# POWER_Ctrl.net
KiCad netlist of a schematic drawn in Altium Designer
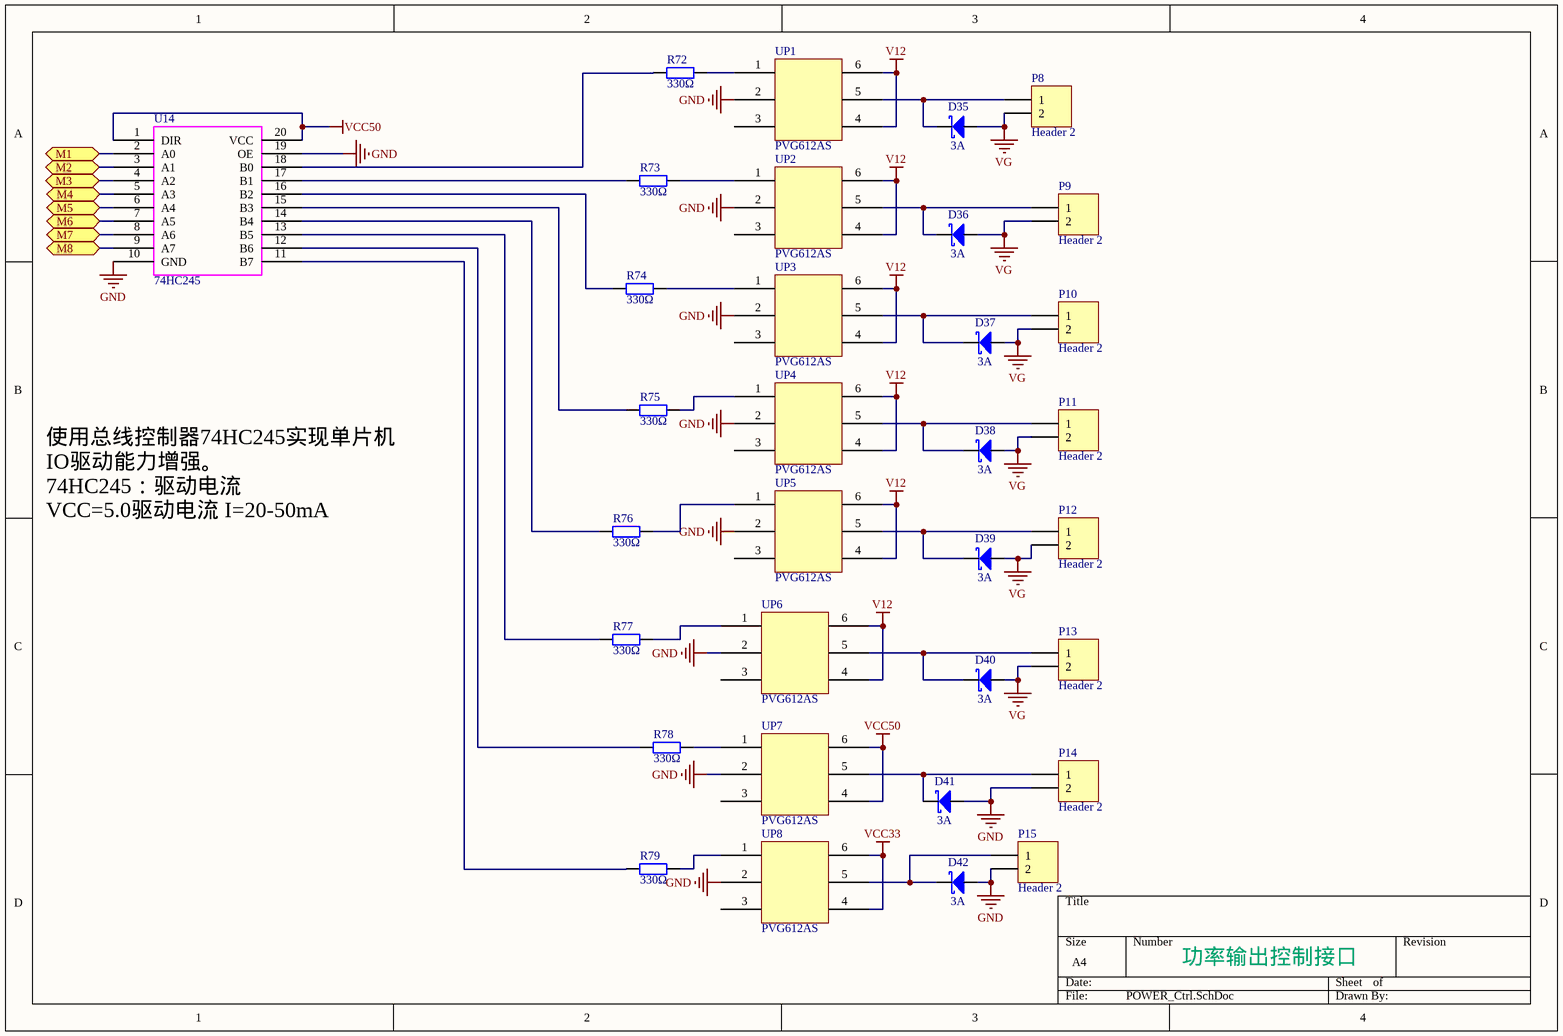
[diagram p0: POWER_Ctrl.SchDoc]

(export (version "E")
  (design (tool "Eeschema 10.0.6"))
  (components
    (comp (ref "D35")
      (value "DiodeSchottky")
      (footprint "SMA")
      (description "Godzilla")
      (fields
        (field (name "GENERACPARTNUMBER") "Temp0036")
        (field (name "MANUFACTURER") "MCC")
        (field (name "DIO CURRENT") "3A")
      )
      (libsource (lib "Jiaoyanyi") (part "DiodeSchottky"))
    )
    (comp (ref "D36")
      (value "DiodeSchottky")
      (footprint "SMA")
      (description "Godzilla")
      (fields
        (field (name "GENERACPARTNUMBER") "Temp0036")
        (field (name "MANUFACTURER") "MCC")
        (field (name "DIO CURRENT") "3A")
      )
      (libsource (lib "Jiaoyanyi") (part "DiodeSchottky"))
    )
    (comp (ref "D37")
      (value "DiodeSchottky")
      (footprint "SMA")
      (description "Godzilla")
      (fields
        (field (name "GENERACPARTNUMBER") "Temp0036")
        (field (name "MANUFACTURER") "MCC")
        (field (name "DIO CURRENT") "3A")
      )
      (libsource (lib "Jiaoyanyi") (part "DiodeSchottky"))
    )
    (comp (ref "D38")
      (value "DiodeSchottky")
      (footprint "SMA")
      (description "Godzilla")
      (fields
        (field (name "GENERACPARTNUMBER") "Temp0036")
        (field (name "MANUFACTURER") "MCC")
        (field (name "DIO CURRENT") "3A")
      )
      (libsource (lib "Jiaoyanyi") (part "DiodeSchottky"))
    )
    (comp (ref "D39")
      (value "DiodeSchottky")
      (footprint "SMA")
      (description "Godzilla")
      (fields
        (field (name "GENERACPARTNUMBER") "Temp0036")
        (field (name "MANUFACTURER") "MCC")
        (field (name "DIO CURRENT") "3A")
      )
      (libsource (lib "Jiaoyanyi") (part "DiodeSchottky"))
    )
    (comp (ref "D40")
      (value "DiodeSchottky")
      (footprint "SMA")
      (description "Godzilla")
      (fields
        (field (name "GENERACPARTNUMBER") "Temp0036")
        (field (name "MANUFACTURER") "MCC")
        (field (name "DIO CURRENT") "3A")
      )
      (libsource (lib "Jiaoyanyi") (part "DiodeSchottky"))
    )
    (comp (ref "D41")
      (value "DiodeSchottky")
      (footprint "SMA")
      (description "Godzilla")
      (fields
        (field (name "GENERACPARTNUMBER") "Temp0036")
        (field (name "MANUFACTURER") "MCC")
        (field (name "DIO CURRENT") "3A")
      )
      (libsource (lib "Jiaoyanyi") (part "DiodeSchottky"))
    )
    (comp (ref "D42")
      (value "DiodeSchottky")
      (footprint "SMA")
      (description "Godzilla")
      (fields
        (field (name "GENERACPARTNUMBER") "Temp0036")
        (field (name "MANUFACTURER") "MCC")
        (field (name "DIO CURRENT") "3A")
      )
      (libsource (lib "Jiaoyanyi") (part "DiodeSchottky"))
    )
    (comp (ref "P8")
      (value "Header 2")
      (footprint "3.81-2P")
      (description "Header, 2-Pin")
      (fields (field (name "PUBLISHER") "Altium Limited"))
      (libsource (lib "Miscellaneous Connectors") (part "Header 2"))
    )
    (comp (ref "P9")
      (value "Header 2")
      (footprint "3.81-2P")
      (description "Header, 2-Pin")
      (fields (field (name "PUBLISHER") "Altium Limited"))
      (libsource (lib "Miscellaneous Connectors") (part "Header 2"))
    )
    (comp (ref "P10")
      (value "Header 2")
      (footprint "3.81-2P")
      (description "Header, 2-Pin")
      (fields (field (name "PUBLISHER") "Altium Limited"))
      (libsource (lib "Miscellaneous Connectors") (part "Header 2"))
    )
    (comp (ref "P11")
      (value "Header 2")
      (footprint "3.81-2P")
      (description "Header, 2-Pin")
      (fields (field (name "PUBLISHER") "Altium Limited"))
      (libsource (lib "Miscellaneous Connectors") (part "Header 2"))
    )
    (comp (ref "P12")
      (value "Header 2")
      (footprint "3.81-2P")
      (description "Header, 2-Pin")
      (fields (field (name "PUBLISHER") "Altium Limited"))
      (libsource (lib "Miscellaneous Connectors") (part "Header 2"))
    )
    (comp (ref "P13")
      (value "Header 2")
      (footprint "3.81-2P")
      (description "Header, 2-Pin")
      (fields (field (name "PUBLISHER") "Altium Limited"))
      (libsource (lib "Miscellaneous Connectors") (part "Header 2"))
    )
    (comp (ref "P14")
      (value "Header 2")
      (footprint "3.81-2P")
      (description "Header, 2-Pin")
      (fields (field (name "PUBLISHER") "Altium Limited"))
      (libsource (lib "Miscellaneous Connectors") (part "Header 2"))
    )
    (comp (ref "P15")
      (value "Header 2")
      (footprint "3.81-2P")
      (description "Header, 2-Pin")
      (fields (field (name "PUBLISHER") "Altium Limited"))
      (libsource (lib "Miscellaneous Connectors") (part "Header 2"))
    )
    (comp (ref "R72")
      (value "330Ω")
      (footprint "1206")
      (description "Resistor")
      (fields (field (name "Comment") "Res2") (field (name "PUBLISHER") "Altium Limited"))
      (libsource (lib "Miscellaneous Devices") (part "Res2"))
    )
    (comp (ref "R73")
      (value "330Ω")
      (footprint "1206")
      (description "Resistor")
      (fields (field (name "Comment") "Res2") (field (name "PUBLISHER") "Altium Limited"))
      (libsource (lib "Miscellaneous Devices") (part "Res2"))
    )
    (comp (ref "R74")
      (value "330Ω")
      (footprint "1206")
      (description "Resistor")
      (fields (field (name "Comment") "Res2") (field (name "PUBLISHER") "Altium Limited"))
      (libsource (lib "Miscellaneous Devices") (part "Res2"))
    )
    (comp (ref "R75")
      (value "330Ω")
      (footprint "1206")
      (description "Resistor")
      (fields (field (name "Comment") "Res2") (field (name "PUBLISHER") "Altium Limited"))
      (libsource (lib "Miscellaneous Devices") (part "Res2"))
    )
    (comp (ref "R76")
      (value "330Ω")
      (footprint "1206")
      (description "Resistor")
      (fields (field (name "Comment") "Res2") (field (name "PUBLISHER") "Altium Limited"))
      (libsource (lib "Miscellaneous Devices") (part "Res2"))
    )
    (comp (ref "R77")
      (value "330Ω")
      (footprint "1206")
      (description "Resistor")
      (fields (field (name "Comment") "Res2") (field (name "PUBLISHER") "Altium Limited"))
      (libsource (lib "Miscellaneous Devices") (part "Res2"))
    )
    (comp (ref "R78")
      (value "330Ω")
      (footprint "1206")
      (description "Resistor")
      (fields (field (name "Comment") "Res2") (field (name "PUBLISHER") "Altium Limited"))
      (libsource (lib "Miscellaneous Devices") (part "Res2"))
    )
    (comp (ref "R79")
      (value "330Ω")
      (footprint "1206")
      (description "Resistor")
      (fields (field (name "Comment") "Res2") (field (name "PUBLISHER") "Altium Limited"))
      (libsource (lib "Miscellaneous Devices") (part "Res2"))
    )
    (comp (ref "U14") (value "74HC245") (footprint "74HC245D") (libsource (lib "74hc245") (part "74HC245")))
    (comp (ref "UP1")
      (value "PVG612AS")
      (footprint "SMD-6")
      (libsource (lib "Active_crystal") (part "PVG612AS"))
    )
    (comp (ref "UP2")
      (value "PVG612AS")
      (footprint "SMD-6")
      (libsource (lib "Active_crystal") (part "PVG612AS"))
    )
    (comp (ref "UP3")
      (value "PVG612AS")
      (footprint "SMD-6")
      (libsource (lib "Active_crystal") (part "PVG612AS"))
    )
    (comp (ref "UP4")
      (value "PVG612AS")
      (footprint "SMD-6")
      (libsource (lib "Active_crystal") (part "PVG612AS"))
    )
    (comp (ref "UP5")
      (value "PVG612AS")
      (footprint "SMD-6")
      (libsource (lib "Active_crystal") (part "PVG612AS"))
    )
    (comp (ref "UP6")
      (value "PVG612AS")
      (footprint "SMD-6")
      (libsource (lib "Active_crystal") (part "PVG612AS"))
    )
    (comp (ref "UP7")
      (value "PVG612AS")
      (footprint "SMD-6")
      (libsource (lib "Active_crystal") (part "PVG612AS"))
    )
    (comp (ref "UP8")
      (value "PVG612AS")
      (footprint "SMD-6")
      (libsource (lib "Active_crystal") (part "PVG612AS"))
    )
  )
  (nets
    (net (code "1") (name "/M1") (class "Default")
      (node (ref "U14") (pin "2") (pinfunction "A0_2") (pintype "passive"))
    )
    (net (code "2") (name "/M2") (class "Default")
      (node (ref "U14") (pin "3") (pinfunction "A1_3") (pintype "passive"))
    )
    (net (code "3") (name "/M3") (class "Default")
      (node (ref "U14") (pin "4") (pinfunction "A2_4") (pintype "passive"))
    )
    (net (code "4") (name "/M4") (class "Default")
      (node (ref "U14") (pin "5") (pinfunction "A3_5") (pintype "passive"))
    )
    (net (code "5") (name "/M5") (class "Default")
      (node (ref "U14") (pin "6") (pinfunction "A4_6") (pintype "passive"))
    )
    (net (code "6") (name "/M6") (class "Default")
      (node (ref "U14") (pin "7") (pinfunction "A5_7") (pintype "passive"))
    )
    (net (code "7") (name "/M7") (class "Default")
      (node (ref "U14") (pin "8") (pinfunction "A6_8") (pintype "passive"))
    )
    (net (code "8") (name "/M8") (class "Default")
      (node (ref "U14") (pin "9") (pinfunction "A7_9") (pintype "passive"))
    )
    (net (code "9") (name "GND") (class "Default")
      (node (ref "D41") (pin "1") (pinfunction "1_1") (pintype "passive"))
      (node (ref "D42") (pin "1") (pinfunction "1_1") (pintype "passive"))
      (node (ref "P14") (pin "2") (pinfunction "2_2") (pintype "passive"))
      (node (ref "P15") (pin "2") (pinfunction "2_2") (pintype "passive"))
      (node (ref "U14") (pin "10") (pinfunction "GND_10") (pintype "passive"))
      (node (ref "U14") (pin "19") (pinfunction "OE_19") (pintype "passive"))
      (node (ref "UP1") (pin "2") (pinfunction "2_2") (pintype "passive"))
      (node (ref "UP2") (pin "2") (pinfunction "2_2") (pintype "passive"))
      (node (ref "UP3") (pin "2") (pinfunction "2_2") (pintype "passive"))
      (node (ref "UP4") (pin "2") (pinfunction "2_2") (pintype "passive"))
      (node (ref "UP5") (pin "2") (pinfunction "2_2") (pintype "passive"))
      (node (ref "UP6") (pin "2") (pinfunction "2_2") (pintype "passive"))
      (node (ref "UP7") (pin "2") (pinfunction "2_2") (pintype "passive"))
      (node (ref "UP8") (pin "2") (pinfunction "2_2") (pintype "passive"))
    )
    (net (code "10") (name "Net-(D35-Pad2)") (class "Default")
      (node (ref "D35") (pin "2") (pinfunction "2_2") (pintype "passive"))
      (node (ref "P8") (pin "1") (pinfunction "1_1") (pintype "passive"))
      (node (ref "UP1") (pin "5") (pinfunction "5_5") (pintype "passive"))
    )
    (net (code "11") (name "Net-(D36-Pad2)") (class "Default")
      (node (ref "D36") (pin "2") (pinfunction "2_2") (pintype "passive"))
      (node (ref "P9") (pin "1") (pinfunction "1_1") (pintype "passive"))
      (node (ref "UP2") (pin "5") (pinfunction "5_5") (pintype "passive"))
    )
    (net (code "12") (name "Net-(D37-Pad2)") (class "Default")
      (node (ref "D37") (pin "2") (pinfunction "2_2") (pintype "passive"))
      (node (ref "P10") (pin "1") (pinfunction "1_1") (pintype "passive"))
      (node (ref "UP3") (pin "5") (pinfunction "5_5") (pintype "passive"))
    )
    (net (code "13") (name "Net-(D38-Pad2)") (class "Default")
      (node (ref "D38") (pin "2") (pinfunction "2_2") (pintype "passive"))
      (node (ref "P11") (pin "1") (pinfunction "1_1") (pintype "passive"))
      (node (ref "UP4") (pin "5") (pinfunction "5_5") (pintype "passive"))
    )
    (net (code "14") (name "Net-(D39-Pad2)") (class "Default")
      (node (ref "D39") (pin "2") (pinfunction "2_2") (pintype "passive"))
      (node (ref "P12") (pin "1") (pinfunction "1_1") (pintype "passive"))
      (node (ref "UP5") (pin "5") (pinfunction "5_5") (pintype "passive"))
    )
    (net (code "15") (name "Net-(D40-Pad2)") (class "Default")
      (node (ref "D40") (pin "2") (pinfunction "2_2") (pintype "passive"))
      (node (ref "P13") (pin "1") (pinfunction "1_1") (pintype "passive"))
      (node (ref "UP6") (pin "5") (pinfunction "5_5") (pintype "passive"))
    )
    (net (code "16") (name "Net-(D41-Pad2)") (class "Default")
      (node (ref "D41") (pin "2") (pinfunction "2_2") (pintype "passive"))
      (node (ref "P14") (pin "1") (pinfunction "1_1") (pintype "passive"))
      (node (ref "UP7") (pin "5") (pinfunction "5_5") (pintype "passive"))
    )
    (net (code "17") (name "Net-(D42-Pad2)") (class "Default")
      (node (ref "D42") (pin "2") (pinfunction "2_2") (pintype "passive"))
      (node (ref "P15") (pin "1") (pinfunction "1_1") (pintype "passive"))
      (node (ref "UP8") (pin "5") (pinfunction "5_5") (pintype "passive"))
    )
    (net (code "18") (name "Net-(R72-Pad1)") (class "Default")
      (node (ref "R72") (pin "1") (pinfunction "1_1") (pintype "passive"))
      (node (ref "UP1") (pin "1") (pinfunction "1_1") (pintype "passive"))
    )
    (net (code "19") (name "Net-(R73-Pad1)") (class "Default")
      (node (ref "R73") (pin "1") (pinfunction "1_1") (pintype "passive"))
      (node (ref "UP2") (pin "1") (pinfunction "1_1") (pintype "passive"))
    )
    (net (code "20") (name "Net-(R74-Pad1)") (class "Default")
      (node (ref "R74") (pin "1") (pinfunction "1_1") (pintype "passive"))
      (node (ref "UP3") (pin "1") (pinfunction "1_1") (pintype "passive"))
    )
    (net (code "21") (name "Net-(R75-Pad1)") (class "Default")
      (node (ref "R75") (pin "1") (pinfunction "1_1") (pintype "passive"))
      (node (ref "UP4") (pin "1") (pinfunction "1_1") (pintype "passive"))
    )
    (net (code "22") (name "Net-(R76-Pad1)") (class "Default")
      (node (ref "R76") (pin "1") (pinfunction "1_1") (pintype "passive"))
      (node (ref "UP5") (pin "1") (pinfunction "1_1") (pintype "passive"))
    )
    (net (code "23") (name "Net-(R77-Pad1)") (class "Default")
      (node (ref "R77") (pin "1") (pinfunction "1_1") (pintype "passive"))
      (node (ref "UP6") (pin "1") (pinfunction "1_1") (pintype "passive"))
    )
    (net (code "24") (name "Net-(R78-Pad1)") (class "Default")
      (node (ref "R78") (pin "1") (pinfunction "1_1") (pintype "passive"))
      (node (ref "UP7") (pin "1") (pinfunction "1_1") (pintype "passive"))
    )
    (net (code "25") (name "Net-(R79-Pad1)") (class "Default")
      (node (ref "R79") (pin "1") (pinfunction "1_1") (pintype "passive"))
      (node (ref "UP8") (pin "1") (pinfunction "1_1") (pintype "passive"))
    )
    (net (code "26") (name "Net-(U14-B0)") (class "Default")
      (node (ref "R72") (pin "2") (pinfunction "2_2") (pintype "passive"))
      (node (ref "U14") (pin "18") (pinfunction "B0_18") (pintype "passive"))
    )
    (net (code "27") (name "Net-(U14-B1)") (class "Default")
      (node (ref "R73") (pin "2") (pinfunction "2_2") (pintype "passive"))
      (node (ref "U14") (pin "17") (pinfunction "B1_17") (pintype "passive"))
    )
    (net (code "28") (name "Net-(U14-B2)") (class "Default")
      (node (ref "R74") (pin "2") (pinfunction "2_2") (pintype "passive"))
      (node (ref "U14") (pin "16") (pinfunction "B2_16") (pintype "passive"))
    )
    (net (code "29") (name "Net-(U14-B3)") (class "Default")
      (node (ref "R75") (pin "2") (pinfunction "2_2") (pintype "passive"))
      (node (ref "U14") (pin "15") (pinfunction "B3_15") (pintype "passive"))
    )
    (net (code "30") (name "Net-(U14-B4)") (class "Default")
      (node (ref "R76") (pin "2") (pinfunction "2_2") (pintype "passive"))
      (node (ref "U14") (pin "14") (pinfunction "B4_14") (pintype "passive"))
    )
    (net (code "31") (name "Net-(U14-B5)") (class "Default")
      (node (ref "R77") (pin "2") (pinfunction "2_2") (pintype "passive"))
      (node (ref "U14") (pin "13") (pinfunction "B5_13") (pintype "passive"))
    )
    (net (code "32") (name "Net-(U14-B6)") (class "Default")
      (node (ref "R78") (pin "2") (pinfunction "2_2") (pintype "passive"))
      (node (ref "U14") (pin "12") (pinfunction "B6_12") (pintype "passive"))
    )
    (net (code "33") (name "Net-(U14-B7)") (class "Default")
      (node (ref "R79") (pin "2") (pinfunction "2_2") (pintype "passive"))
      (node (ref "U14") (pin "11") (pinfunction "B7_11") (pintype "passive"))
    )
    (net (code "34") (name "V12") (class "Default")
      (node (ref "UP1") (pin "4") (pinfunction "4_4") (pintype "passive"))
      (node (ref "UP1") (pin "6") (pinfunction "6_6") (pintype "passive"))
      (node (ref "UP2") (pin "4") (pinfunction "4_4") (pintype "passive"))
      (node (ref "UP2") (pin "6") (pinfunction "6_6") (pintype "passive"))
      (node (ref "UP3") (pin "4") (pinfunction "4_4") (pintype "passive"))
      (node (ref "UP3") (pin "6") (pinfunction "6_6") (pintype "passive"))
      (node (ref "UP4") (pin "4") (pinfunction "4_4") (pintype "passive"))
      (node (ref "UP4") (pin "6") (pinfunction "6_6") (pintype "passive"))
      (node (ref "UP5") (pin "4") (pinfunction "4_4") (pintype "passive"))
      (node (ref "UP5") (pin "6") (pinfunction "6_6") (pintype "passive"))
      (node (ref "UP6") (pin "4") (pinfunction "4_4") (pintype "passive"))
      (node (ref "UP6") (pin "6") (pinfunction "6_6") (pintype "passive"))
    )
    (net (code "35") (name "VCC33") (class "Default")
      (node (ref "UP8") (pin "4") (pinfunction "4_4") (pintype "passive"))
      (node (ref "UP8") (pin "6") (pinfunction "6_6") (pintype "passive"))
    )
    (net (code "36") (name "VCC50") (class "Default")
      (node (ref "U14") (pin "1") (pinfunction "DIR_1") (pintype "passive"))
      (node (ref "U14") (pin "20") (pinfunction "VCC_20") (pintype "passive"))
      (node (ref "UP7") (pin "4") (pinfunction "4_4") (pintype "passive"))
      (node (ref "UP7") (pin "6") (pinfunction "6_6") (pintype "passive"))
    )
    (net (code "37") (name "VG") (class "Default")
      (node (ref "D35") (pin "1") (pinfunction "1_1") (pintype "passive"))
      (node (ref "D36") (pin "1") (pinfunction "1_1") (pintype "passive"))
      (node (ref "D37") (pin "1") (pinfunction "1_1") (pintype "passive"))
      (node (ref "D38") (pin "1") (pinfunction "1_1") (pintype "passive"))
      (node (ref "D39") (pin "1") (pinfunction "1_1") (pintype "passive"))
      (node (ref "D40") (pin "1") (pinfunction "1_1") (pintype "passive"))
      (node (ref "P10") (pin "2") (pinfunction "2_2") (pintype "passive"))
      (node (ref "P11") (pin "2") (pinfunction "2_2") (pintype "passive"))
      (node (ref "P12") (pin "2") (pinfunction "2_2") (pintype "passive"))
      (node (ref "P13") (pin "2") (pinfunction "2_2") (pintype "passive"))
      (node (ref "P8") (pin "2") (pinfunction "2_2") (pintype "passive"))
      (node (ref "P9") (pin "2") (pinfunction "2_2") (pintype "passive"))
    )
    (net (code "38") (name "unconnected-(UP1-Pad3)") (class "Default")
      (node (ref "UP1") (pin "3") (pinfunction "3_3") (pintype "passive"))
    )
    (net (code "39") (name "unconnected-(UP2-Pad3)") (class "Default")
      (node (ref "UP2") (pin "3") (pinfunction "3_3") (pintype "passive"))
    )
    (net (code "40") (name "unconnected-(UP3-Pad3)") (class "Default")
      (node (ref "UP3") (pin "3") (pinfunction "3_3") (pintype "passive"))
    )
    (net (code "41") (name "unconnected-(UP4-Pad3)") (class "Default")
      (node (ref "UP4") (pin "3") (pinfunction "3_3") (pintype "passive"))
    )
    (net (code "42") (name "unconnected-(UP5-Pad3)") (class "Default")
      (node (ref "UP5") (pin "3") (pinfunction "3_3") (pintype "passive"))
    )
    (net (code "43") (name "unconnected-(UP6-Pad3)") (class "Default")
      (node (ref "UP6") (pin "3") (pinfunction "3_3") (pintype "passive"))
    )
    (net (code "44") (name "unconnected-(UP7-Pad3)") (class "Default")
      (node (ref "UP7") (pin "3") (pinfunction "3_3") (pintype "passive"))
    )
    (net (code "45") (name "unconnected-(UP8-Pad3)") (class "Default")
      (node (ref "UP8") (pin "3") (pinfunction "3_3") (pintype "passive"))
    )
  )
)
